# PowerBoard.net
KiCad netlist of a schematic drawn in EAGLE
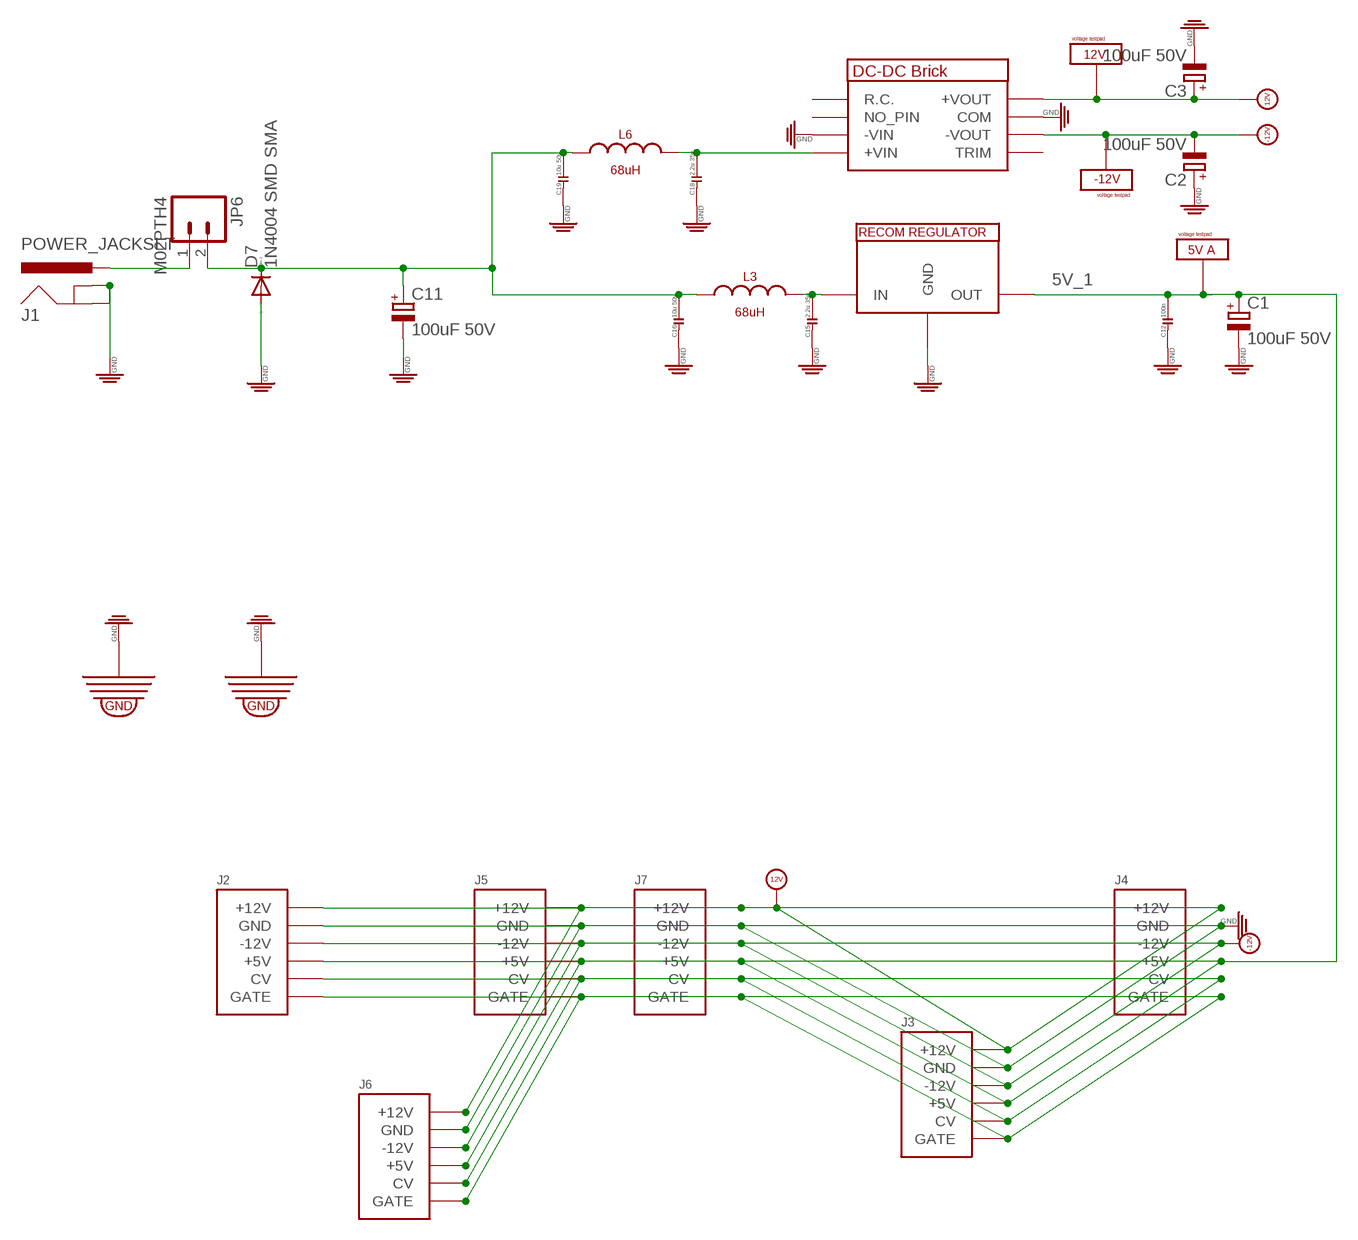
[diagram p0: schematic, sheet 2]

(export (version "E")
  (design (tool "Eeschema 10.0.6"))
  (components
    (comp (ref "C1")
      (value "100uF 50V")
      (footprint "eagle-import:153CLV-1010")
      (libsource (lib "eagle-import") (part "CPOL-EU153CLV-1010"))
    )
    (comp (ref "C2")
      (value "100uF 50V")
      (footprint "eagle-import:153CLV-1010")
      (libsource (lib "eagle-import") (part "CPOL-EU153CLV-1010"))
    )
    (comp (ref "C3")
      (value "100uF 50V")
      (footprint "eagle-import:153CLV-1010")
      (libsource (lib "eagle-import") (part "CPOL-EU153CLV-1010"))
    )
    (comp (ref "C11")
      (value "100uF 50V")
      (footprint "eagle-import:153CLV-1010")
      (libsource (lib "eagle-import") (part "CPOL-EU153CLV-1010"))
    )
    (comp (ref "C12")
      (value "100n")
      (footprint "eagle-import:C0603")
      (libsource (lib "eagle-import") (part "C-0603"))
    )
    (comp (ref "C15")
      (value "2.2u 35v")
      (footprint "eagle-import:C0603")
      (libsource (lib "eagle-import") (part "C-0603"))
    )
    (comp (ref "C16")
      (value "10u 50v")
      (footprint "eagle-import:C0603")
      (libsource (lib "eagle-import") (part "C-0603"))
    )
    (comp (ref "C18")
      (value "2.2u 35v")
      (footprint "eagle-import:C0603")
      (libsource (lib "eagle-import") (part "C-0603"))
    )
    (comp (ref "C19")
      (value "10u 50v")
      (footprint "eagle-import:C0603")
      (libsource (lib "eagle-import") (part "C-0603"))
    )
    (comp (ref "D7")
      (value "1N4004 SMD SMA")
      (footprint "eagle-import:DO214AC")
      (libsource (lib "eagle-import") (part "DIODE-DO214AC"))
    )
    (comp (ref "J1")
      (value "POWER_JACKSLT")
      (footprint "eagle-import:POWER_JACK_SLOT")
      (libsource (lib "eagle-import") (part "POWER_JACKSLT"))
    )
    (comp (ref "J2")
      (value "POWERSHROUDED")
      (footprint "eagle-import:POWER_16_SHROUDED")
      (libsource (lib "eagle-import") (part "POWERSHROUDED"))
    )
    (comp (ref "J3")
      (value "POWERSHROUDED")
      (footprint "eagle-import:POWER_16_SHROUDED")
      (libsource (lib "eagle-import") (part "POWERSHROUDED"))
    )
    (comp (ref "J4")
      (value "POWERSHROUDED")
      (footprint "eagle-import:POWER_16_SHROUDED")
      (libsource (lib "eagle-import") (part "POWERSHROUDED"))
    )
    (comp (ref "J5")
      (value "POWERSHROUDED")
      (footprint "eagle-import:POWER_16_SHROUDED")
      (libsource (lib "eagle-import") (part "POWERSHROUDED"))
    )
    (comp (ref "J6")
      (value "POWERSHROUDED")
      (footprint "eagle-import:POWER_16_SHROUDED")
      (libsource (lib "eagle-import") (part "POWERSHROUDED"))
    )
    (comp (ref "J7")
      (value "POWERSHROUDED")
      (footprint "eagle-import:POWER_16_SHROUDED")
      (libsource (lib "eagle-import") (part "POWERSHROUDED"))
    )
    (comp (ref "JP6")
      (value "M02PTH4")
      (footprint "eagle-import:1X02_XTRA_BIG")
      (libsource (lib "eagle-import") (part "M02PTH4"))
    )
    (comp (ref "L3")
      (value "68uH")
      (footprint "eagle-import:SWRB120XS")
      (libsource (lib "eagle-import") (part "L-SWRB1204S"))
    )
    (comp (ref "L6")
      (value "68uH")
      (footprint "eagle-import:SWRB120XS")
      (libsource (lib "eagle-import") (part "L-SWRB1204S"))
    )
    (comp (ref "U$1")
      (value "DKA30")
      (footprint "eagle-import:MEANWELL_DKA30")
      (libsource (lib "eagle-import") (part "DKA30"))
    )
    (comp (ref "U$17")
      (value "RECOM_REGULATOR")
      (footprint "eagle-import:R-78E5.0-1.0")
      (libsource (lib "eagle-import") (part "RECOM_REGULATOR"))
    )
    (comp (ref "U$19")
      (value "GNDLOOP")
      (footprint "eagle-import:GROUNDLOOP")
      (libsource (lib "eagle-import") (part "GNDLOOP"))
    )
    (comp (ref "U$22")
      (value "GNDLOOP")
      (footprint "eagle-import:GROUNDLOOP")
      (libsource (lib "eagle-import") (part "GNDLOOP"))
    )
    (comp (ref "U$23")
      (value "VOLTAGETESTPAD")
      (footprint "eagle-import:POWERTESTPAD")
      (fields (field (name "DESC") "12V"))
      (libsource (lib "eagle-import") (part "VOLTAGETESTPAD"))
    )
    (comp (ref "U$25")
      (value "VOLTAGETESTPAD")
      (footprint "eagle-import:POWERTESTPAD")
      (fields (field (name "DESC") "5V A"))
      (libsource (lib "eagle-import") (part "VOLTAGETESTPAD"))
    )
    (comp (ref "U$28")
      (value "VOLTAGETESTPAD")
      (footprint "eagle-import:POWERTESTPAD")
      (fields (field (name "DESC") "-12V"))
      (libsource (lib "eagle-import") (part "VOLTAGETESTPAD"))
    )
  )
  (nets
    (net (code "1") (name "-12V") (class "Default")
      (node (ref "C2") (pin "-") (pinfunction "-_-") (pintype "passive"))
      (node (ref "J2") (pin "1") (pinfunction "-12V_1") (pintype "bidirectional"))
      (node (ref "J2") (pin "2") (pinfunction "-12V_2") (pintype "bidirectional"))
      (node (ref "J3") (pin "1") (pinfunction "-12V_1") (pintype "bidirectional"))
      (node (ref "J3") (pin "2") (pinfunction "-12V_2") (pintype "bidirectional"))
      (node (ref "J4") (pin "1") (pinfunction "-12V_1") (pintype "bidirectional"))
      (node (ref "J4") (pin "2") (pinfunction "-12V_2") (pintype "bidirectional"))
      (node (ref "J5") (pin "1") (pinfunction "-12V_1") (pintype "bidirectional"))
      (node (ref "J5") (pin "2") (pinfunction "-12V_2") (pintype "bidirectional"))
      (node (ref "J6") (pin "1") (pinfunction "-12V_1") (pintype "bidirectional"))
      (node (ref "J6") (pin "2") (pinfunction "-12V_2") (pintype "bidirectional"))
      (node (ref "J7") (pin "1") (pinfunction "-12V_1") (pintype "bidirectional"))
      (node (ref "J7") (pin "2") (pinfunction "-12V_2") (pintype "bidirectional"))
      (node (ref "U$1") (pin "P$7") (pinfunction "-VOUT_P$7") (pintype "bidirectional"))
      (node (ref "U$28") (pin "P$1") (pinfunction "VOLTAGE_P$1") (pintype "bidirectional"))
      (node (ref "U$28") (pin "P$2") (pinfunction "VOLTAGE_P$2") (pintype "bidirectional"))
      (node (ref "U$28") (pin "P$3") (pinfunction "VOLTAGE_P$3") (pintype "bidirectional"))
    )
    (net (code "2") (name "5V_1") (class "Default")
      (node (ref "C1") (pin "+") (pinfunction "+_+") (pintype "passive"))
      (node (ref "C12") (pin "2") (pinfunction "2_2") (pintype "bidirectional"))
      (node (ref "J2") (pin "11") (pinfunction "+5V_11") (pintype "bidirectional"))
      (node (ref "J2") (pin "12") (pinfunction "+5V_12") (pintype "bidirectional"))
      (node (ref "J3") (pin "11") (pinfunction "+5V_11") (pintype "bidirectional"))
      (node (ref "J3") (pin "12") (pinfunction "+5V_12") (pintype "bidirectional"))
      (node (ref "J4") (pin "11") (pinfunction "+5V_11") (pintype "bidirectional"))
      (node (ref "J4") (pin "12") (pinfunction "+5V_12") (pintype "bidirectional"))
      (node (ref "J5") (pin "11") (pinfunction "+5V_11") (pintype "bidirectional"))
      (node (ref "J5") (pin "12") (pinfunction "+5V_12") (pintype "bidirectional"))
      (node (ref "J6") (pin "11") (pinfunction "+5V_11") (pintype "bidirectional"))
      (node (ref "J6") (pin "12") (pinfunction "+5V_12") (pintype "bidirectional"))
      (node (ref "J7") (pin "11") (pinfunction "+5V_11") (pintype "bidirectional"))
      (node (ref "J7") (pin "12") (pinfunction "+5V_12") (pintype "bidirectional"))
      (node (ref "U$17") (pin "P$3") (pinfunction "OUT_P$3") (pintype "bidirectional"))
      (node (ref "U$25") (pin "P$1") (pinfunction "VOLTAGE_P$1") (pintype "bidirectional"))
      (node (ref "U$25") (pin "P$2") (pinfunction "VOLTAGE_P$2") (pintype "bidirectional"))
      (node (ref "U$25") (pin "P$3") (pinfunction "VOLTAGE_P$3") (pintype "bidirectional"))
    )
    (net (code "3") (name "12V") (class "Default")
      (node (ref "C3") (pin "+") (pinfunction "+_+") (pintype "passive"))
      (node (ref "J2") (pin "10") (pinfunction "+12V_10") (pintype "bidirectional"))
      (node (ref "J2") (pin "9") (pinfunction "+12V_9") (pintype "bidirectional"))
      (node (ref "J3") (pin "10") (pinfunction "+12V_10") (pintype "bidirectional"))
      (node (ref "J3") (pin "9") (pinfunction "+12V_9") (pintype "bidirectional"))
      (node (ref "J4") (pin "10") (pinfunction "+12V_10") (pintype "bidirectional"))
      (node (ref "J4") (pin "9") (pinfunction "+12V_9") (pintype "bidirectional"))
      (node (ref "J5") (pin "10") (pinfunction "+12V_10") (pintype "bidirectional"))
      (node (ref "J5") (pin "9") (pinfunction "+12V_9") (pintype "bidirectional"))
      (node (ref "J6") (pin "10") (pinfunction "+12V_10") (pintype "bidirectional"))
      (node (ref "J6") (pin "9") (pinfunction "+12V_9") (pintype "bidirectional"))
      (node (ref "J7") (pin "10") (pinfunction "+12V_10") (pintype "bidirectional"))
      (node (ref "J7") (pin "9") (pinfunction "+12V_9") (pintype "bidirectional"))
      (node (ref "U$1") (pin "P$5") (pinfunction "+VOUT_P$5") (pintype "bidirectional"))
      (node (ref "U$23") (pin "P$1") (pinfunction "VOLTAGE_P$1") (pintype "bidirectional"))
      (node (ref "U$23") (pin "P$2") (pinfunction "VOLTAGE_P$2") (pintype "bidirectional"))
      (node (ref "U$23") (pin "P$3") (pinfunction "VOLTAGE_P$3") (pintype "bidirectional"))
    )
    (net (code "4") (name "GND") (class "Default")
      (node (ref "C1") (pin "-") (pinfunction "-_-") (pintype "passive"))
      (node (ref "C11") (pin "-") (pinfunction "-_-") (pintype "passive"))
      (node (ref "C12") (pin "1") (pinfunction "1_1") (pintype "bidirectional"))
      (node (ref "C15") (pin "1") (pinfunction "1_1") (pintype "bidirectional"))
      (node (ref "C16") (pin "1") (pinfunction "1_1") (pintype "bidirectional"))
      (node (ref "C18") (pin "1") (pinfunction "1_1") (pintype "bidirectional"))
      (node (ref "C19") (pin "1") (pinfunction "1_1") (pintype "bidirectional"))
      (node (ref "C2") (pin "+") (pinfunction "+_+") (pintype "passive"))
      (node (ref "C3") (pin "-") (pinfunction "-_-") (pintype "passive"))
      (node (ref "D7") (pin "A") (pinfunction "A_A") (pintype "passive"))
      (node (ref "J1") (pin "GND@1") (pinfunction "GNDBREAK_GND@1") (pintype "bidirectional"))
      (node (ref "J1") (pin "GND@2") (pinfunction "GND_GND@2") (pintype "bidirectional"))
      (node (ref "J2") (pin "3") (pinfunction "GND_3") (pintype "bidirectional"))
      (node (ref "J2") (pin "4") (pinfunction "GND_4") (pintype "bidirectional"))
      (node (ref "J2") (pin "5") (pinfunction "GND_5") (pintype "bidirectional"))
      (node (ref "J2") (pin "6") (pinfunction "GND_6") (pintype "bidirectional"))
      (node (ref "J2") (pin "7") (pinfunction "GND_7") (pintype "bidirectional"))
      (node (ref "J2") (pin "8") (pinfunction "GND_8") (pintype "bidirectional"))
      (node (ref "J3") (pin "3") (pinfunction "GND_3") (pintype "bidirectional"))
      (node (ref "J3") (pin "4") (pinfunction "GND_4") (pintype "bidirectional"))
      (node (ref "J3") (pin "5") (pinfunction "GND_5") (pintype "bidirectional"))
      (node (ref "J3") (pin "6") (pinfunction "GND_6") (pintype "bidirectional"))
      (node (ref "J3") (pin "7") (pinfunction "GND_7") (pintype "bidirectional"))
      (node (ref "J3") (pin "8") (pinfunction "GND_8") (pintype "bidirectional"))
      (node (ref "J4") (pin "3") (pinfunction "GND_3") (pintype "bidirectional"))
      (node (ref "J4") (pin "4") (pinfunction "GND_4") (pintype "bidirectional"))
      (node (ref "J4") (pin "5") (pinfunction "GND_5") (pintype "bidirectional"))
      (node (ref "J4") (pin "6") (pinfunction "GND_6") (pintype "bidirectional"))
      (node (ref "J4") (pin "7") (pinfunction "GND_7") (pintype "bidirectional"))
      (node (ref "J4") (pin "8") (pinfunction "GND_8") (pintype "bidirectional"))
      (node (ref "J5") (pin "3") (pinfunction "GND_3") (pintype "bidirectional"))
      (node (ref "J5") (pin "4") (pinfunction "GND_4") (pintype "bidirectional"))
      (node (ref "J5") (pin "5") (pinfunction "GND_5") (pintype "bidirectional"))
      (node (ref "J5") (pin "6") (pinfunction "GND_6") (pintype "bidirectional"))
      (node (ref "J5") (pin "7") (pinfunction "GND_7") (pintype "bidirectional"))
      (node (ref "J5") (pin "8") (pinfunction "GND_8") (pintype "bidirectional"))
      (node (ref "J6") (pin "3") (pinfunction "GND_3") (pintype "bidirectional"))
      (node (ref "J6") (pin "4") (pinfunction "GND_4") (pintype "bidirectional"))
      (node (ref "J6") (pin "5") (pinfunction "GND_5") (pintype "bidirectional"))
      (node (ref "J6") (pin "6") (pinfunction "GND_6") (pintype "bidirectional"))
      (node (ref "J6") (pin "7") (pinfunction "GND_7") (pintype "bidirectional"))
      (node (ref "J6") (pin "8") (pinfunction "GND_8") (pintype "bidirectional"))
      (node (ref "J7") (pin "3") (pinfunction "GND_3") (pintype "bidirectional"))
      (node (ref "J7") (pin "4") (pinfunction "GND_4") (pintype "bidirectional"))
      (node (ref "J7") (pin "5") (pinfunction "GND_5") (pintype "bidirectional"))
      (node (ref "J7") (pin "6") (pinfunction "GND_6") (pintype "bidirectional"))
      (node (ref "J7") (pin "7") (pinfunction "GND_7") (pintype "bidirectional"))
      (node (ref "J7") (pin "8") (pinfunction "GND_8") (pintype "bidirectional"))
      (node (ref "U$1") (pin "P$3") (pinfunction "-VIN_P$3") (pintype "bidirectional"))
      (node (ref "U$1") (pin "P$6") (pinfunction "COM_P$6") (pintype "bidirectional"))
      (node (ref "U$17") (pin "P$2") (pinfunction "GND_P$2") (pintype "bidirectional"))
      (node (ref "U$19") (pin "P$1") (pinfunction "P$1_P$1") (pintype "bidirectional"))
      (node (ref "U$19") (pin "P$2") (pinfunction "P$1_P$2") (pintype "bidirectional"))
      (node (ref "U$22") (pin "P$1") (pinfunction "P$1_P$1") (pintype "bidirectional"))
      (node (ref "U$22") (pin "P$2") (pinfunction "P$1_P$2") (pintype "bidirectional"))
    )
    (net (code "5") (name "Net-(C11-Pad+)") (class "Default")
      (node (ref "C11") (pin "+") (pinfunction "+_+") (pintype "passive"))
      (node (ref "C16") (pin "2") (pinfunction "2_2") (pintype "bidirectional"))
      (node (ref "C19") (pin "2") (pinfunction "2_2") (pintype "bidirectional"))
      (node (ref "D7") (pin "C") (pinfunction "C_C") (pintype "passive"))
      (node (ref "JP6") (pin "2") (pinfunction "2_2") (pintype "passive"))
      (node (ref "L3") (pin "P$1") (pinfunction "P$1_P$1") (pintype "bidirectional"))
      (node (ref "L6") (pin "P$1") (pinfunction "P$1_P$1") (pintype "bidirectional"))
    )
    (net (code "6") (name "Net-(J1-PadPWR)") (class "Default")
      (node (ref "J1") (pin "PWR") (pinfunction "PWR_PWR") (pintype "bidirectional"))
      (node (ref "JP6") (pin "1") (pinfunction "1_1") (pintype "passive"))
    )
    (net (code "7") (name "Net-(J2-CV-Pad13)") (class "Default")
      (node (ref "J2") (pin "13") (pinfunction "CV_13") (pintype "bidirectional"))
      (node (ref "J2") (pin "14") (pinfunction "CV_14") (pintype "bidirectional"))
      (node (ref "J3") (pin "13") (pinfunction "CV_13") (pintype "bidirectional"))
      (node (ref "J3") (pin "14") (pinfunction "CV_14") (pintype "bidirectional"))
      (node (ref "J4") (pin "13") (pinfunction "CV_13") (pintype "bidirectional"))
      (node (ref "J4") (pin "14") (pinfunction "CV_14") (pintype "bidirectional"))
      (node (ref "J5") (pin "13") (pinfunction "CV_13") (pintype "bidirectional"))
      (node (ref "J5") (pin "14") (pinfunction "CV_14") (pintype "bidirectional"))
      (node (ref "J6") (pin "13") (pinfunction "CV_13") (pintype "bidirectional"))
      (node (ref "J6") (pin "14") (pinfunction "CV_14") (pintype "bidirectional"))
      (node (ref "J7") (pin "13") (pinfunction "CV_13") (pintype "bidirectional"))
      (node (ref "J7") (pin "14") (pinfunction "CV_14") (pintype "bidirectional"))
    )
    (net (code "8") (name "Net-(J2-GATE-Pad15)") (class "Default")
      (node (ref "J2") (pin "15") (pinfunction "GATE_15") (pintype "bidirectional"))
      (node (ref "J2") (pin "16") (pinfunction "GATE_16") (pintype "bidirectional"))
      (node (ref "J3") (pin "15") (pinfunction "GATE_15") (pintype "bidirectional"))
      (node (ref "J3") (pin "16") (pinfunction "GATE_16") (pintype "bidirectional"))
      (node (ref "J4") (pin "15") (pinfunction "GATE_15") (pintype "bidirectional"))
      (node (ref "J4") (pin "16") (pinfunction "GATE_16") (pintype "bidirectional"))
      (node (ref "J5") (pin "15") (pinfunction "GATE_15") (pintype "bidirectional"))
      (node (ref "J5") (pin "16") (pinfunction "GATE_16") (pintype "bidirectional"))
      (node (ref "J6") (pin "15") (pinfunction "GATE_15") (pintype "bidirectional"))
      (node (ref "J6") (pin "16") (pinfunction "GATE_16") (pintype "bidirectional"))
      (node (ref "J7") (pin "15") (pinfunction "GATE_15") (pintype "bidirectional"))
      (node (ref "J7") (pin "16") (pinfunction "GATE_16") (pintype "bidirectional"))
    )
    (net (code "9") (name "Net-(U$1-+VIN)") (class "Default")
      (node (ref "C18") (pin "2") (pinfunction "2_2") (pintype "bidirectional"))
      (node (ref "L6") (pin "P$2") (pinfunction "P$2_P$2") (pintype "bidirectional"))
      (node (ref "U$1") (pin "P$4") (pinfunction "+VIN_P$4") (pintype "bidirectional"))
    )
    (net (code "10") (name "Net-(U$17-IN)") (class "Default")
      (node (ref "C15") (pin "2") (pinfunction "2_2") (pintype "bidirectional"))
      (node (ref "L3") (pin "P$2") (pinfunction "P$2_P$2") (pintype "bidirectional"))
      (node (ref "U$17") (pin "P$1") (pinfunction "IN_P$1") (pintype "bidirectional"))
    )
    (net (code "11") (name "unconnected-(U$1-NO_PIN-PadP$2)") (class "Default")
      (node (ref "U$1") (pin "P$2") (pinfunction "NO_PIN_P$2") (pintype "bidirectional"))
    )
    (net (code "12") (name "unconnected-(U$1-R.C.-PadP$1)") (class "Default")
      (node (ref "U$1") (pin "P$1") (pinfunction "R.C._P$1") (pintype "bidirectional"))
    )
    (net (code "13") (name "unconnected-(U$1-TRIM-PadP$8)") (class "Default")
      (node (ref "U$1") (pin "P$8") (pinfunction "TRIM_P$8") (pintype "bidirectional"))
    )
  )
)
